# B2B_Connector.net
KiCad netlist of a schematic drawn in Altium Designer
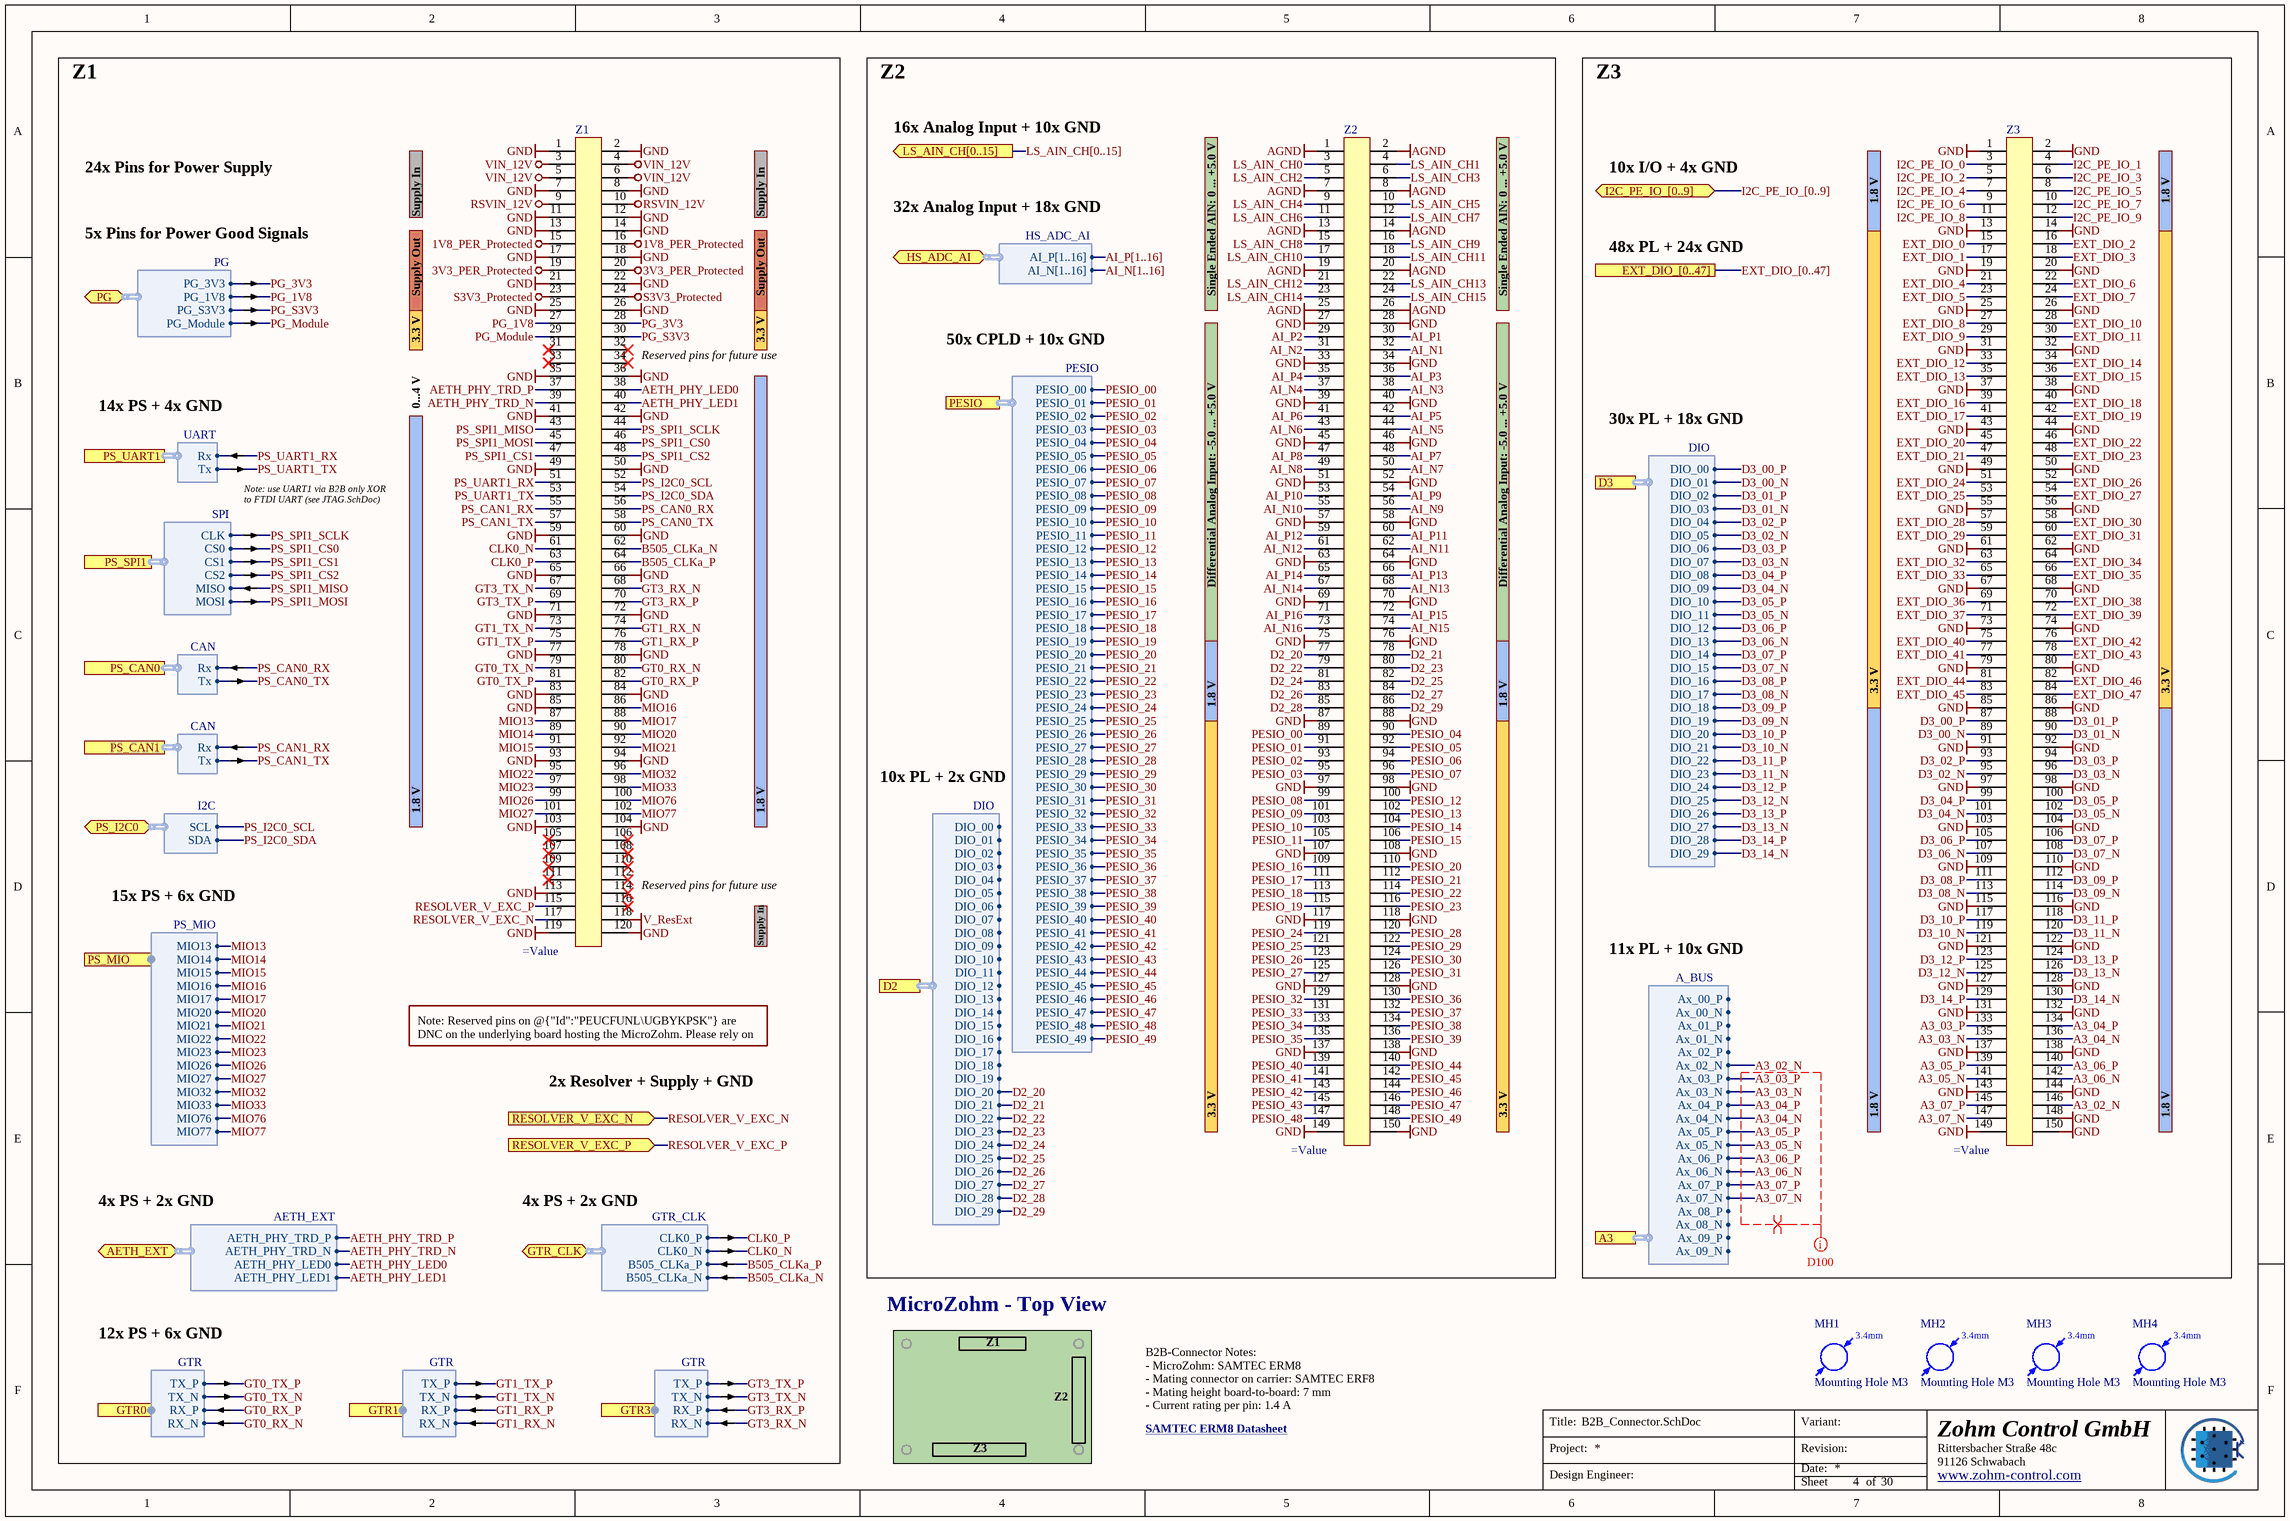
[diagram p0: B2B_Connector.SchDoc]

(export (version "E")
  (design (tool "Eeschema 10.0.6"))
  (components
    (comp (ref "MH1")
      (value "Mounting Hole M3")
      (footprint "MH_3.4")
      (description "Mounting Hole")
      (fields (field (name "CREATED FROM") "MHlatky"))
      (libsource (lib "user") (part "Mounting Hole"))
    )
    (comp (ref "MH2")
      (value "Mounting Hole M3")
      (footprint "MH_3.4")
      (description "Mounting Hole")
      (fields (field (name "CREATED FROM") "MHlatky"))
      (libsource (lib "user") (part "Mounting Hole"))
    )
    (comp (ref "MH3")
      (value "Mounting Hole M3")
      (footprint "MH_3.4")
      (description "Mounting Hole")
      (fields (field (name "CREATED FROM") "MHlatky"))
      (libsource (lib "user") (part "Mounting Hole"))
    )
    (comp (ref "MH4")
      (value "Mounting Hole M3")
      (footprint "MH_3.4")
      (description "Mounting Hole")
      (fields (field (name "CREATED FROM") "MHlatky"))
      (libsource (lib "user") (part "Mounting Hole"))
    )
    (comp (ref "Z1")
      (value "~")
      (footprint "ERM8-060-02.0-L-DV")
      (description "0.80 mm Edge Rate Rugged High Speed")
      (fields
        (field (name "MANUFACTURER PART NUMBER") "ERM8-060-02.0-L-DV-TR")
        (field (name "MANUFACTURER") "SAMTEC")
        (field (name "CREATED FROM") "AGeiger")
      )
      (libsource (lib "user") (part "CON-120"))
    )
    (comp (ref "Z2")
      (value "~")
      (footprint "ERM8-075-02.0-L-DV")
      (description "0.80 mm Edge Rate Rugged High Speed")
      (fields
        (field (name "MANUFACTURER PART NUMBER") "ERM8-075-02.0-L-DV-TR")
        (field (name "MANUFACTURER") "SAMTEC")
        (field (name "CREATED FROM") "AGeiger")
      )
      (libsource (lib "user") (part "CON-150"))
    )
    (comp (ref "Z3")
      (value "~")
      (footprint "ERM8-075-02.0-L-DV")
      (description "0.80 mm Edge Rate Rugged High Speed")
      (fields
        (field (name "MANUFACTURER PART NUMBER") "ERM8-075-02.0-L-DV-TR")
        (field (name "MANUFACTURER") "SAMTEC")
        (field (name "CREATED FROM") "AGeiger")
      )
      (libsource (lib "user") (part "CON-150"))
    )
  )
  (nets
    (net (code "14") (name "/A3_02_N") (class "Default")
      (node (ref "Z3") (pin "146") (pinfunction "146_146") (pintype "passive"))
    )
    (net (code "15") (name "/A3_03_N") (class "Default")
      (node (ref "Z3") (pin "135") (pinfunction "135_135") (pintype "passive"))
    )
    (net (code "16") (name "/A3_03_P") (class "Default")
      (node (ref "Z3") (pin "133") (pinfunction "133_133") (pintype "passive"))
    )
    (net (code "17") (name "/A3_04_N") (class "Default")
      (node (ref "Z3") (pin "136") (pinfunction "136_136") (pintype "passive"))
    )
    (net (code "18") (name "/A3_04_P") (class "Default")
      (node (ref "Z3") (pin "134") (pinfunction "134_134") (pintype "passive"))
    )
    (net (code "19") (name "/A3_05_N") (class "Default")
      (node (ref "Z3") (pin "141") (pinfunction "141_141") (pintype "passive"))
    )
    (net (code "20") (name "/A3_05_P") (class "Default")
      (node (ref "Z3") (pin "139") (pinfunction "139_139") (pintype "passive"))
    )
    (net (code "21") (name "/A3_06_N") (class "Default")
      (node (ref "Z3") (pin "142") (pinfunction "142_142") (pintype "passive"))
    )
    (net (code "22") (name "/A3_06_P") (class "Default")
      (node (ref "Z3") (pin "140") (pinfunction "140_140") (pintype "passive"))
    )
    (net (code "23") (name "/A3_07_N") (class "Default")
      (node (ref "Z3") (pin "147") (pinfunction "147_147") (pintype "passive"))
    )
    (net (code "24") (name "/A3_07_P") (class "Default")
      (node (ref "Z3") (pin "145") (pinfunction "145_145") (pintype "passive"))
    )
    (net (code "25") (name "/AETH_PHY_LED0") (class "Default")
      (node (ref "Z1") (pin "38") (pinfunction "38_38") (pintype "passive"))
    )
    (net (code "26") (name "/AETH_PHY_LED1") (class "Default")
      (node (ref "Z1") (pin "40") (pinfunction "40_40") (pintype "passive"))
    )
    (net (code "27") (name "/AETH_PHY_TRD_N") (class "Default")
      (node (ref "Z1") (pin "39") (pinfunction "39_39") (pintype "passive"))
    )
    (net (code "28") (name "/AETH_PHY_TRD_P") (class "Default")
      (node (ref "Z1") (pin "37") (pinfunction "37_37") (pintype "passive"))
    )
    (net (code "29") (name "/AI_N1") (class "Default")
      (node (ref "Z2") (pin "32") (pinfunction "32_32") (pintype "passive"))
    )
    (net (code "30") (name "/AI_N2") (class "Default")
      (node (ref "Z2") (pin "31") (pinfunction "31_31") (pintype "passive"))
    )
    (net (code "31") (name "/AI_N3") (class "Default")
      (node (ref "Z2") (pin "38") (pinfunction "38_38") (pintype "passive"))
    )
    (net (code "32") (name "/AI_N4") (class "Default")
      (node (ref "Z2") (pin "37") (pinfunction "37_37") (pintype "passive"))
    )
    (net (code "33") (name "/AI_N5") (class "Default")
      (node (ref "Z2") (pin "44") (pinfunction "44_44") (pintype "passive"))
    )
    (net (code "34") (name "/AI_N6") (class "Default")
      (node (ref "Z2") (pin "43") (pinfunction "43_43") (pintype "passive"))
    )
    (net (code "35") (name "/AI_N7") (class "Default")
      (node (ref "Z2") (pin "50") (pinfunction "50_50") (pintype "passive"))
    )
    (net (code "36") (name "/AI_N8") (class "Default")
      (node (ref "Z2") (pin "49") (pinfunction "49_49") (pintype "passive"))
    )
    (net (code "37") (name "/AI_N9") (class "Default")
      (node (ref "Z2") (pin "56") (pinfunction "56_56") (pintype "passive"))
    )
    (net (code "38") (name "/AI_N10") (class "Default")
      (node (ref "Z2") (pin "55") (pinfunction "55_55") (pintype "passive"))
    )
    (net (code "39") (name "/AI_N11") (class "Default")
      (node (ref "Z2") (pin "62") (pinfunction "62_62") (pintype "passive"))
    )
    (net (code "40") (name "/AI_N12") (class "Default")
      (node (ref "Z2") (pin "61") (pinfunction "61_61") (pintype "passive"))
    )
    (net (code "41") (name "/AI_N13") (class "Default")
      (node (ref "Z2") (pin "68") (pinfunction "68_68") (pintype "passive"))
    )
    (net (code "42") (name "/AI_N14") (class "Default")
      (node (ref "Z2") (pin "67") (pinfunction "67_67") (pintype "passive"))
    )
    (net (code "43") (name "/AI_N15") (class "Default")
      (node (ref "Z2") (pin "74") (pinfunction "74_74") (pintype "passive"))
    )
    (net (code "44") (name "/AI_N16") (class "Default")
      (node (ref "Z2") (pin "73") (pinfunction "73_73") (pintype "passive"))
    )
    (net (code "46") (name "/AI_P1") (class "Default")
      (node (ref "Z2") (pin "30") (pinfunction "30_30") (pintype "passive"))
    )
    (net (code "47") (name "/AI_P2") (class "Default")
      (node (ref "Z2") (pin "29") (pinfunction "29_29") (pintype "passive"))
    )
    (net (code "48") (name "/AI_P3") (class "Default")
      (node (ref "Z2") (pin "36") (pinfunction "36_36") (pintype "passive"))
    )
    (net (code "49") (name "/AI_P4") (class "Default")
      (node (ref "Z2") (pin "35") (pinfunction "35_35") (pintype "passive"))
    )
    (net (code "50") (name "/AI_P5") (class "Default")
      (node (ref "Z2") (pin "42") (pinfunction "42_42") (pintype "passive"))
    )
    (net (code "51") (name "/AI_P6") (class "Default")
      (node (ref "Z2") (pin "41") (pinfunction "41_41") (pintype "passive"))
    )
    (net (code "52") (name "/AI_P7") (class "Default")
      (node (ref "Z2") (pin "48") (pinfunction "48_48") (pintype "passive"))
    )
    (net (code "53") (name "/AI_P8") (class "Default")
      (node (ref "Z2") (pin "47") (pinfunction "47_47") (pintype "passive"))
    )
    (net (code "54") (name "/AI_P9") (class "Default")
      (node (ref "Z2") (pin "54") (pinfunction "54_54") (pintype "passive"))
    )
    (net (code "55") (name "/AI_P10") (class "Default")
      (node (ref "Z2") (pin "53") (pinfunction "53_53") (pintype "passive"))
    )
    (net (code "56") (name "/AI_P11") (class "Default")
      (node (ref "Z2") (pin "60") (pinfunction "60_60") (pintype "passive"))
    )
    (net (code "57") (name "/AI_P12") (class "Default")
      (node (ref "Z2") (pin "59") (pinfunction "59_59") (pintype "passive"))
    )
    (net (code "58") (name "/AI_P13") (class "Default")
      (node (ref "Z2") (pin "66") (pinfunction "66_66") (pintype "passive"))
    )
    (net (code "59") (name "/AI_P14") (class "Default")
      (node (ref "Z2") (pin "65") (pinfunction "65_65") (pintype "passive"))
    )
    (net (code "60") (name "/AI_P15") (class "Default")
      (node (ref "Z2") (pin "72") (pinfunction "72_72") (pintype "passive"))
    )
    (net (code "61") (name "/AI_P16") (class "Default")
      (node (ref "Z2") (pin "71") (pinfunction "71_71") (pintype "passive"))
    )
    (net (code "63") (name "/B505_CLKa_N") (class "Default")
      (node (ref "Z1") (pin "62") (pinfunction "62_62") (pintype "passive"))
    )
    (net (code "64") (name "/B505_CLKa_P") (class "Default")
      (node (ref "Z1") (pin "64") (pinfunction "64_64") (pintype "passive"))
    )
    (net (code "65") (name "/CLK0_N") (class "Default")
      (node (ref "Z1") (pin "61") (pinfunction "61_61") (pintype "passive"))
    )
    (net (code "66") (name "/CLK0_P") (class "Default")
      (node (ref "Z1") (pin "63") (pinfunction "63_63") (pintype "passive"))
    )
    (net (code "67") (name "/D2_20") (class "Default")
      (node (ref "Z2") (pin "77") (pinfunction "77_77") (pintype "passive"))
    )
    (net (code "68") (name "/D2_21") (class "Default")
      (node (ref "Z2") (pin "78") (pinfunction "78_78") (pintype "passive"))
    )
    (net (code "69") (name "/D2_22") (class "Default")
      (node (ref "Z2") (pin "79") (pinfunction "79_79") (pintype "passive"))
    )
    (net (code "70") (name "/D2_23") (class "Default")
      (node (ref "Z2") (pin "80") (pinfunction "80_80") (pintype "passive"))
    )
    (net (code "71") (name "/D2_24") (class "Default")
      (node (ref "Z2") (pin "81") (pinfunction "81_81") (pintype "passive"))
    )
    (net (code "72") (name "/D2_25") (class "Default")
      (node (ref "Z2") (pin "82") (pinfunction "82_82") (pintype "passive"))
    )
    (net (code "73") (name "/D2_26") (class "Default")
      (node (ref "Z2") (pin "83") (pinfunction "83_83") (pintype "passive"))
    )
    (net (code "74") (name "/D2_27") (class "Default")
      (node (ref "Z2") (pin "84") (pinfunction "84_84") (pintype "passive"))
    )
    (net (code "75") (name "/D2_28") (class "Default")
      (node (ref "Z2") (pin "85") (pinfunction "85_85") (pintype "passive"))
    )
    (net (code "76") (name "/D2_29") (class "Default")
      (node (ref "Z2") (pin "86") (pinfunction "86_86") (pintype "passive"))
    )
    (net (code "77") (name "/D3_00_N") (class "Default")
      (node (ref "Z3") (pin "89") (pinfunction "89_89") (pintype "passive"))
    )
    (net (code "78") (name "/D3_00_P") (class "Default")
      (node (ref "Z3") (pin "87") (pinfunction "87_87") (pintype "passive"))
    )
    (net (code "79") (name "/D3_01_N") (class "Default")
      (node (ref "Z3") (pin "90") (pinfunction "90_90") (pintype "passive"))
    )
    (net (code "80") (name "/D3_01_P") (class "Default")
      (node (ref "Z3") (pin "88") (pinfunction "88_88") (pintype "passive"))
    )
    (net (code "81") (name "/D3_02_N") (class "Default")
      (node (ref "Z3") (pin "95") (pinfunction "95_95") (pintype "passive"))
    )
    (net (code "82") (name "/D3_02_P") (class "Default")
      (node (ref "Z3") (pin "93") (pinfunction "93_93") (pintype "passive"))
    )
    (net (code "83") (name "/D3_03_N") (class "Default")
      (node (ref "Z3") (pin "96") (pinfunction "96_96") (pintype "passive"))
    )
    (net (code "84") (name "/D3_03_P") (class "Default")
      (node (ref "Z3") (pin "94") (pinfunction "94_94") (pintype "passive"))
    )
    (net (code "85") (name "/D3_04_N") (class "Default")
      (node (ref "Z3") (pin "101") (pinfunction "101_101") (pintype "passive"))
    )
    (net (code "86") (name "/D3_04_P") (class "Default")
      (node (ref "Z3") (pin "99") (pinfunction "99_99") (pintype "passive"))
    )
    (net (code "87") (name "/D3_05_N") (class "Default")
      (node (ref "Z3") (pin "102") (pinfunction "102_102") (pintype "passive"))
    )
    (net (code "88") (name "/D3_05_P") (class "Default")
      (node (ref "Z3") (pin "100") (pinfunction "100_100") (pintype "passive"))
    )
    (net (code "89") (name "/D3_06_N") (class "Default")
      (node (ref "Z3") (pin "107") (pinfunction "107_107") (pintype "passive"))
    )
    (net (code "90") (name "/D3_06_P") (class "Default")
      (node (ref "Z3") (pin "105") (pinfunction "105_105") (pintype "passive"))
    )
    (net (code "91") (name "/D3_07_N") (class "Default")
      (node (ref "Z3") (pin "108") (pinfunction "108_108") (pintype "passive"))
    )
    (net (code "92") (name "/D3_07_P") (class "Default")
      (node (ref "Z3") (pin "106") (pinfunction "106_106") (pintype "passive"))
    )
    (net (code "93") (name "/D3_08_N") (class "Default")
      (node (ref "Z3") (pin "113") (pinfunction "113_113") (pintype "passive"))
    )
    (net (code "94") (name "/D3_08_P") (class "Default")
      (node (ref "Z3") (pin "111") (pinfunction "111_111") (pintype "passive"))
    )
    (net (code "95") (name "/D3_09_N") (class "Default")
      (node (ref "Z3") (pin "114") (pinfunction "114_114") (pintype "passive"))
    )
    (net (code "96") (name "/D3_09_P") (class "Default")
      (node (ref "Z3") (pin "112") (pinfunction "112_112") (pintype "passive"))
    )
    (net (code "97") (name "/D3_10_N") (class "Default")
      (node (ref "Z3") (pin "119") (pinfunction "119_119") (pintype "passive"))
    )
    (net (code "98") (name "/D3_10_P") (class "Default")
      (node (ref "Z3") (pin "117") (pinfunction "117_117") (pintype "passive"))
    )
    (net (code "99") (name "/D3_11_N") (class "Default")
      (node (ref "Z3") (pin "120") (pinfunction "120_120") (pintype "passive"))
    )
    (net (code "100") (name "/D3_11_P") (class "Default")
      (node (ref "Z3") (pin "118") (pinfunction "118_118") (pintype "passive"))
    )
    (net (code "101") (name "/D3_12_N") (class "Default")
      (node (ref "Z3") (pin "125") (pinfunction "125_125") (pintype "passive"))
    )
    (net (code "102") (name "/D3_12_P") (class "Default")
      (node (ref "Z3") (pin "123") (pinfunction "123_123") (pintype "passive"))
    )
    (net (code "103") (name "/D3_13_N") (class "Default")
      (node (ref "Z3") (pin "126") (pinfunction "126_126") (pintype "passive"))
    )
    (net (code "104") (name "/D3_13_P") (class "Default")
      (node (ref "Z3") (pin "124") (pinfunction "124_124") (pintype "passive"))
    )
    (net (code "105") (name "/D3_14_N") (class "Default")
      (node (ref "Z3") (pin "130") (pinfunction "130_130") (pintype "passive"))
    )
    (net (code "106") (name "/D3_14_P") (class "Default")
      (node (ref "Z3") (pin "129") (pinfunction "129_129") (pintype "passive"))
    )
    (net (code "107") (name "/EXT_DIO_0") (class "Default")
      (node (ref "Z3") (pin "15") (pinfunction "15_15") (pintype "passive"))
    )
    (net (code "108") (name "/EXT_DIO_1") (class "Default")
      (node (ref "Z3") (pin "17") (pinfunction "17_17") (pintype "passive"))
    )
    (net (code "109") (name "/EXT_DIO_2") (class "Default")
      (node (ref "Z3") (pin "16") (pinfunction "16_16") (pintype "passive"))
    )
    (net (code "110") (name "/EXT_DIO_3") (class "Default")
      (node (ref "Z3") (pin "18") (pinfunction "18_18") (pintype "passive"))
    )
    (net (code "111") (name "/EXT_DIO_4") (class "Default")
      (node (ref "Z3") (pin "21") (pinfunction "21_21") (pintype "passive"))
    )
    (net (code "112") (name "/EXT_DIO_5") (class "Default")
      (node (ref "Z3") (pin "23") (pinfunction "23_23") (pintype "passive"))
    )
    (net (code "113") (name "/EXT_DIO_6") (class "Default")
      (node (ref "Z3") (pin "22") (pinfunction "22_22") (pintype "passive"))
    )
    (net (code "114") (name "/EXT_DIO_7") (class "Default")
      (node (ref "Z3") (pin "24") (pinfunction "24_24") (pintype "passive"))
    )
    (net (code "115") (name "/EXT_DIO_8") (class "Default")
      (node (ref "Z3") (pin "27") (pinfunction "27_27") (pintype "passive"))
    )
    (net (code "116") (name "/EXT_DIO_9") (class "Default")
      (node (ref "Z3") (pin "29") (pinfunction "29_29") (pintype "passive"))
    )
    (net (code "117") (name "/EXT_DIO_10") (class "Default")
      (node (ref "Z3") (pin "28") (pinfunction "28_28") (pintype "passive"))
    )
    (net (code "118") (name "/EXT_DIO_11") (class "Default")
      (node (ref "Z3") (pin "30") (pinfunction "30_30") (pintype "passive"))
    )
    (net (code "119") (name "/EXT_DIO_12") (class "Default")
      (node (ref "Z3") (pin "33") (pinfunction "33_33") (pintype "passive"))
    )
    (net (code "120") (name "/EXT_DIO_13") (class "Default")
      (node (ref "Z3") (pin "35") (pinfunction "35_35") (pintype "passive"))
    )
    (net (code "121") (name "/EXT_DIO_14") (class "Default")
      (node (ref "Z3") (pin "34") (pinfunction "34_34") (pintype "passive"))
    )
    (net (code "122") (name "/EXT_DIO_15") (class "Default")
      (node (ref "Z3") (pin "36") (pinfunction "36_36") (pintype "passive"))
    )
    (net (code "123") (name "/EXT_DIO_16") (class "Default")
      (node (ref "Z3") (pin "39") (pinfunction "39_39") (pintype "passive"))
    )
    (net (code "124") (name "/EXT_DIO_17") (class "Default")
      (node (ref "Z3") (pin "41") (pinfunction "41_41") (pintype "passive"))
    )
    (net (code "125") (name "/EXT_DIO_18") (class "Default")
      (node (ref "Z3") (pin "40") (pinfunction "40_40") (pintype "passive"))
    )
    (net (code "126") (name "/EXT_DIO_19") (class "Default")
      (node (ref "Z3") (pin "42") (pinfunction "42_42") (pintype "passive"))
    )
    (net (code "127") (name "/EXT_DIO_20") (class "Default")
      (node (ref "Z3") (pin "45") (pinfunction "45_45") (pintype "passive"))
    )
    (net (code "128") (name "/EXT_DIO_21") (class "Default")
      (node (ref "Z3") (pin "47") (pinfunction "47_47") (pintype "passive"))
    )
    (net (code "129") (name "/EXT_DIO_22") (class "Default")
      (node (ref "Z3") (pin "46") (pinfunction "46_46") (pintype "passive"))
    )
    (net (code "130") (name "/EXT_DIO_23") (class "Default")
      (node (ref "Z3") (pin "48") (pinfunction "48_48") (pintype "passive"))
    )
    (net (code "131") (name "/EXT_DIO_24") (class "Default")
      (node (ref "Z3") (pin "51") (pinfunction "51_51") (pintype "passive"))
    )
    (net (code "132") (name "/EXT_DIO_25") (class "Default")
      (node (ref "Z3") (pin "53") (pinfunction "53_53") (pintype "passive"))
    )
    (net (code "133") (name "/EXT_DIO_26") (class "Default")
      (node (ref "Z3") (pin "52") (pinfunction "52_52") (pintype "passive"))
    )
    (net (code "134") (name "/EXT_DIO_27") (class "Default")
      (node (ref "Z3") (pin "54") (pinfunction "54_54") (pintype "passive"))
    )
    (net (code "135") (name "/EXT_DIO_28") (class "Default")
      (node (ref "Z3") (pin "57") (pinfunction "57_57") (pintype "passive"))
    )
    (net (code "136") (name "/EXT_DIO_29") (class "Default")
      (node (ref "Z3") (pin "59") (pinfunction "59_59") (pintype "passive"))
    )
    (net (code "137") (name "/EXT_DIO_30") (class "Default")
      (node (ref "Z3") (pin "58") (pinfunction "58_58") (pintype "passive"))
    )
    (net (code "138") (name "/EXT_DIO_31") (class "Default")
      (node (ref "Z3") (pin "60") (pinfunction "60_60") (pintype "passive"))
    )
    (net (code "139") (name "/EXT_DIO_32") (class "Default")
      (node (ref "Z3") (pin "63") (pinfunction "63_63") (pintype "passive"))
    )
    (net (code "140") (name "/EXT_DIO_33") (class "Default")
      (node (ref "Z3") (pin "65") (pinfunction "65_65") (pintype "passive"))
    )
    (net (code "141") (name "/EXT_DIO_34") (class "Default")
      (node (ref "Z3") (pin "64") (pinfunction "64_64") (pintype "passive"))
    )
    (net (code "142") (name "/EXT_DIO_35") (class "Default")
      (node (ref "Z3") (pin "66") (pinfunction "66_66") (pintype "passive"))
    )
    (net (code "143") (name "/EXT_DIO_36") (class "Default")
      (node (ref "Z3") (pin "69") (pinfunction "69_69") (pintype "passive"))
    )
    (net (code "144") (name "/EXT_DIO_37") (class "Default")
      (node (ref "Z3") (pin "71") (pinfunction "71_71") (pintype "passive"))
    )
    (net (code "145") (name "/EXT_DIO_38") (class "Default")
      (node (ref "Z3") (pin "70") (pinfunction "70_70") (pintype "passive"))
    )
    (net (code "146") (name "/EXT_DIO_39") (class "Default")
      (node (ref "Z3") (pin "72") (pinfunction "72_72") (pintype "passive"))
    )
    (net (code "147") (name "/EXT_DIO_40") (class "Default")
      (node (ref "Z3") (pin "75") (pinfunction "75_75") (pintype "passive"))
    )
    (net (code "148") (name "/EXT_DIO_41") (class "Default")
      (node (ref "Z3") (pin "77") (pinfunction "77_77") (pintype "passive"))
    )
    (net (code "149") (name "/EXT_DIO_42") (class "Default")
      (node (ref "Z3") (pin "76") (pinfunction "76_76") (pintype "passive"))
    )
    (net (code "150") (name "/EXT_DIO_43") (class "Default")
      (node (ref "Z3") (pin "78") (pinfunction "78_78") (pintype "passive"))
    )
    (net (code "151") (name "/EXT_DIO_44") (class "Default")
      (node (ref "Z3") (pin "81") (pinfunction "81_81") (pintype "passive"))
    )
    (net (code "152") (name "/EXT_DIO_45") (class "Default")
      (node (ref "Z3") (pin "83") (pinfunction "83_83") (pintype "passive"))
    )
    (net (code "153") (name "/EXT_DIO_46") (class "Default")
      (node (ref "Z3") (pin "82") (pinfunction "82_82") (pintype "passive"))
    )
    (net (code "154") (name "/EXT_DIO_47") (class "Default")
      (node (ref "Z3") (pin "84") (pinfunction "84_84") (pintype "passive"))
    )
    (net (code "156") (name "/GT0_RX_N") (class "Default")
      (node (ref "Z1") (pin "80") (pinfunction "80_80") (pintype "passive"))
    )
    (net (code "157") (name "/GT0_RX_P") (class "Default")
      (node (ref "Z1") (pin "82") (pinfunction "82_82") (pintype "passive"))
    )
    (net (code "158") (name "/GT0_TX_N") (class "Default")
      (node (ref "Z1") (pin "79") (pinfunction "79_79") (pintype "passive"))
    )
    (net (code "159") (name "/GT0_TX_P") (class "Default")
      (node (ref "Z1") (pin "81") (pinfunction "81_81") (pintype "passive"))
    )
    (net (code "160") (name "/GT1_RX_N") (class "Default")
      (node (ref "Z1") (pin "74") (pinfunction "74_74") (pintype "passive"))
    )
    (net (code "161") (name "/GT1_RX_P") (class "Default")
      (node (ref "Z1") (pin "76") (pinfunction "76_76") (pintype "passive"))
    )
    (net (code "162") (name "/GT1_TX_N") (class "Default")
      (node (ref "Z1") (pin "73") (pinfunction "73_73") (pintype "passive"))
    )
    (net (code "163") (name "/GT1_TX_P") (class "Default")
      (node (ref "Z1") (pin "75") (pinfunction "75_75") (pintype "passive"))
    )
    (net (code "164") (name "/GT3_RX_N") (class "Default")
      (node (ref "Z1") (pin "68") (pinfunction "68_68") (pintype "passive"))
    )
    (net (code "165") (name "/GT3_RX_P") (class "Default")
      (node (ref "Z1") (pin "70") (pinfunction "70_70") (pintype "passive"))
    )
    (net (code "166") (name "/GT3_TX_N") (class "Default")
      (node (ref "Z1") (pin "67") (pinfunction "67_67") (pintype "passive"))
    )
    (net (code "167") (name "/GT3_TX_P") (class "Default")
      (node (ref "Z1") (pin "69") (pinfunction "69_69") (pintype "passive"))
    )
    (net (code "168") (name "/I2C_PE_IO_0") (class "Default")
      (node (ref "Z3") (pin "3") (pinfunction "3_3") (pintype "passive"))
    )
    (net (code "169") (name "/I2C_PE_IO_1") (class "Default")
      (node (ref "Z3") (pin "4") (pinfunction "4_4") (pintype "passive"))
    )
    (net (code "170") (name "/I2C_PE_IO_2") (class "Default")
      (node (ref "Z3") (pin "5") (pinfunction "5_5") (pintype "passive"))
    )
    (net (code "171") (name "/I2C_PE_IO_3") (class "Default")
      (node (ref "Z3") (pin "6") (pinfunction "6_6") (pintype "passive"))
    )
    (net (code "172") (name "/I2C_PE_IO_4") (class "Default")
      (node (ref "Z3") (pin "7") (pinfunction "7_7") (pintype "passive"))
    )
    (net (code "173") (name "/I2C_PE_IO_5") (class "Default")
      (node (ref "Z3") (pin "8") (pinfunction "8_8") (pintype "passive"))
    )
    (net (code "174") (name "/I2C_PE_IO_6") (class "Default")
      (node (ref "Z3") (pin "9") (pinfunction "9_9") (pintype "passive"))
    )
    (net (code "175") (name "/I2C_PE_IO_7") (class "Default")
      (node (ref "Z3") (pin "10") (pinfunction "10_10") (pintype "passive"))
    )
    (net (code "176") (name "/I2C_PE_IO_8") (class "Default")
      (node (ref "Z3") (pin "11") (pinfunction "11_11") (pintype "passive"))
    )
    (net (code "177") (name "/I2C_PE_IO_9") (class "Default")
      (node (ref "Z3") (pin "12") (pinfunction "12_12") (pintype "passive"))
    )
    (net (code "179") (name "/LS_AIN_CH0") (class "Default")
      (node (ref "Z2") (pin "3") (pinfunction "3_3") (pintype "passive"))
    )
    (net (code "180") (name "/LS_AIN_CH1") (class "Default")
      (node (ref "Z2") (pin "4") (pinfunction "4_4") (pintype "passive"))
    )
    (net (code "181") (name "/LS_AIN_CH2") (class "Default")
      (node (ref "Z2") (pin "5") (pinfunction "5_5") (pintype "passive"))
    )
    (net (code "182") (name "/LS_AIN_CH3") (class "Default")
      (node (ref "Z2") (pin "6") (pinfunction "6_6") (pintype "passive"))
    )
    (net (code "183") (name "/LS_AIN_CH4") (class "Default")
      (node (ref "Z2") (pin "9") (pinfunction "9_9") (pintype "passive"))
    )
    (net (code "184") (name "/LS_AIN_CH5") (class "Default")
      (node (ref "Z2") (pin "10") (pinfunction "10_10") (pintype "passive"))
    )
    (net (code "185") (name "/LS_AIN_CH6") (class "Default")
      (node (ref "Z2") (pin "11") (pinfunction "11_11") (pintype "passive"))
    )
    (net (code "186") (name "/LS_AIN_CH7") (class "Default")
      (node (ref "Z2") (pin "12") (pinfunction "12_12") (pintype "passive"))
    )
    (net (code "187") (name "/LS_AIN_CH8") (class "Default")
      (node (ref "Z2") (pin "15") (pinfunction "15_15") (pintype "passive"))
    )
    (net (code "188") (name "/LS_AIN_CH9") (class "Default")
      (node (ref "Z2") (pin "16") (pinfunction "16_16") (pintype "passive"))
    )
    (net (code "189") (name "/LS_AIN_CH10") (class "Default")
      (node (ref "Z2") (pin "17") (pinfunction "17_17") (pintype "passive"))
    )
    (net (code "190") (name "/LS_AIN_CH11") (class "Default")
      (node (ref "Z2") (pin "18") (pinfunction "18_18") (pintype "passive"))
    )
    (net (code "191") (name "/LS_AIN_CH12") (class "Default")
      (node (ref "Z2") (pin "21") (pinfunction "21_21") (pintype "passive"))
    )
    (net (code "192") (name "/LS_AIN_CH13") (class "Default")
      (node (ref "Z2") (pin "22") (pinfunction "22_22") (pintype "passive"))
    )
    (net (code "193") (name "/LS_AIN_CH14") (class "Default")
      (node (ref "Z2") (pin "23") (pinfunction "23_23") (pintype "passive"))
    )
    (net (code "194") (name "/LS_AIN_CH15") (class "Default")
      (node (ref "Z2") (pin "24") (pinfunction "24_24") (pintype "passive"))
    )
    (net (code "196") (name "/MIO13") (class "Default")
      (node (ref "Z1") (pin "87") (pinfunction "87_87") (pintype "passive"))
    )
    (net (code "197") (name "/MIO14") (class "Default")
      (node (ref "Z1") (pin "89") (pinfunction "89_89") (pintype "passive"))
    )
    (net (code "198") (name "/MIO15") (class "Default")
      (node (ref "Z1") (pin "91") (pinfunction "91_91") (pintype "passive"))
    )
    (net (code "199") (name "/MIO16") (class "Default")
      (node (ref "Z1") (pin "86") (pinfunction "86_86") (pintype "passive"))
    )
    (net (code "200") (name "/MIO17") (class "Default")
      (node (ref "Z1") (pin "88") (pinfunction "88_88") (pintype "passive"))
    )
    (net (code "201") (name "/MIO20") (class "Default")
      (node (ref "Z1") (pin "90") (pinfunction "90_90") (pintype "passive"))
    )
    (net (code "202") (name "/MIO21") (class "Default")
      (node (ref "Z1") (pin "92") (pinfunction "92_92") (pintype "passive"))
    )
    (net (code "203") (name "/MIO22") (class "Default")
      (node (ref "Z1") (pin "95") (pinfunction "95_95") (pintype "passive"))
    )
    (net (code "204") (name "/MIO23") (class "Default")
      (node (ref "Z1") (pin "97") (pinfunction "97_97") (pintype "passive"))
    )
    (net (code "205") (name "/MIO26") (class "Default")
      (node (ref "Z1") (pin "99") (pinfunction "99_99") (pintype "passive"))
    )
    (net (code "206") (name "/MIO27") (class "Default")
      (node (ref "Z1") (pin "101") (pinfunction "101_101") (pintype "passive"))
    )
    (net (code "207") (name "/MIO32") (class "Default")
      (node (ref "Z1") (pin "96") (pinfunction "96_96") (pintype "passive"))
    )
    (net (code "208") (name "/MIO33") (class "Default")
      (node (ref "Z1") (pin "98") (pinfunction "98_98") (pintype "passive"))
    )
    (net (code "209") (name "/MIO76") (class "Default")
      (node (ref "Z1") (pin "100") (pinfunction "100_100") (pintype "passive"))
    )
    (net (code "210") (name "/MIO77") (class "Default")
      (node (ref "Z1") (pin "102") (pinfunction "102_102") (pintype "passive"))
    )
    (net (code "211") (name "/PESIO_00") (class "Default")
      (node (ref "Z2") (pin "89") (pinfunction "89_89") (pintype "passive"))
    )
    (net (code "212") (name "/PESIO_01") (class "Default")
      (node (ref "Z2") (pin "91") (pinfunction "91_91") (pintype "passive"))
    )
    (net (code "213") (name "/PESIO_02") (class "Default")
      (node (ref "Z2") (pin "93") (pinfunction "93_93") (pintype "passive"))
    )
    (net (code "214") (name "/PESIO_03") (class "Default")
      (node (ref "Z2") (pin "95") (pinfunction "95_95") (pintype "passive"))
    )
    (net (code "215") (name "/PESIO_04") (class "Default")
      (node (ref "Z2") (pin "90") (pinfunction "90_90") (pintype "passive"))
    )
    (net (code "216") (name "/PESIO_05") (class "Default")
      (node (ref "Z2") (pin "92") (pinfunction "92_92") (pintype "passive"))
    )
    (net (code "217") (name "/PESIO_06") (class "Default")
      (node (ref "Z2") (pin "94") (pinfunction "94_94") (pintype "passive"))
    )
    (net (code "218") (name "/PESIO_07") (class "Default")
      (node (ref "Z2") (pin "96") (pinfunction "96_96") (pintype "passive"))
    )
    (net (code "219") (name "/PESIO_08") (class "Default")
      (node (ref "Z2") (pin "99") (pinfunction "99_99") (pintype "passive"))
    )
    (net (code "220") (name "/PESIO_09") (class "Default")
      (node (ref "Z2") (pin "101") (pinfunction "101_101") (pintype "passive"))
    )
    (net (code "221") (name "/PESIO_10") (class "Default")
      (node (ref "Z2") (pin "103") (pinfunction "103_103") (pintype "passive"))
    )
    (net (code "222") (name "/PESIO_11") (class "Default")
      (node (ref "Z2") (pin "105") (pinfunction "105_105") (pintype "passive"))
    )
    (net (code "223") (name "/PESIO_12") (class "Default")
      (node (ref "Z2") (pin "100") (pinfunction "100_100") (pintype "passive"))
    )
    (net (code "224") (name "/PESIO_13") (class "Default")
      (node (ref "Z2") (pin "102") (pinfunction "102_102") (pintype "passive"))
    )
    (net (code "225") (name "/PESIO_14") (class "Default")
      (node (ref "Z2") (pin "104") (pinfunction "104_104") (pintype "passive"))
    )
    (net (code "226") (name "/PESIO_15") (class "Default")
      (node (ref "Z2") (pin "106") (pinfunction "106_106") (pintype "passive"))
    )
    (net (code "227") (name "/PESIO_16") (class "Default")
      (node (ref "Z2") (pin "109") (pinfunction "109_109") (pintype "passive"))
    )
    (net (code "228") (name "/PESIO_17") (class "Default")
      (node (ref "Z2") (pin "111") (pinfunction "111_111") (pintype "passive"))
    )
    (net (code "229") (name "/PESIO_18") (class "Default")
      (node (ref "Z2") (pin "113") (pinfunction "113_113") (pintype "passive"))
    )
    (net (code "230") (name "/PESIO_19") (class "Default")
      (node (ref "Z2") (pin "115") (pinfunction "115_115") (pintype "passive"))
    )
    (net (code "231") (name "/PESIO_20") (class "Default")
      (node (ref "Z2") (pin "110") (pinfunction "110_110") (pintype "passive"))
    )
    (net (code "232") (name "/PESIO_21") (class "Default")
      (node (ref "Z2") (pin "112") (pinfunction "112_112") (pintype "passive"))
    )
    (net (code "233") (name "/PESIO_22") (class "Default")
      (node (ref "Z2") (pin "114") (pinfunction "114_114") (pintype "passive"))
    )
    (net (code "234") (name "/PESIO_23") (class "Default")
      (node (ref "Z2") (pin "116") (pinfunction "116_116") (pintype "passive"))
    )
    (net (code "235") (name "/PESIO_24") (class "Default")
      (node (ref "Z2") (pin "119") (pinfunction "119_119") (pintype "passive"))
    )
    (net (code "236") (name "/PESIO_25") (class "Default")
      (node (ref "Z2") (pin "121") (pinfunction "121_121") (pintype "passive"))
    )
    (net (code "237") (name "/PESIO_26") (class "Default")
      (node (ref "Z2") (pin "123") (pinfunction "123_123") (pintype "passive"))
    )
    (net (code "238") (name "/PESIO_27") (class "Default")
      (node (ref "Z2") (pin "125") (pinfunction "125_125") (pintype "passive"))
    )
    (net (code "239") (name "/PESIO_28") (class "Default")
      (node (ref "Z2") (pin "120") (pinfunction "120_120") (pintype "passive"))
    )
    (net (code "240") (name "/PESIO_29") (class "Default")
      (node (ref "Z2") (pin "122") (pinfunction "122_122") (pintype "passive"))
    )
    (net (code "241") (name "/PESIO_30") (class "Default")
      (node (ref "Z2") (pin "124") (pinfunction "124_124") (pintype "passive"))
    )
    (net (code "242") (name "/PESIO_31") (class "Default")
      (node (ref "Z2") (pin "126") (pinfunction "126_126") (pintype "passive"))
    )
    (net (code "243") (name "/PESIO_32") (class "Default")
      (node (ref "Z2") (pin "129") (pinfunction "129_129") (pintype "passive"))
    )
    (net (code "244") (name "/PESIO_33") (class "Default")
      (node (ref "Z2") (pin "131") (pinfunction "131_131") (pintype "passive"))
    )
    (net (code "245") (name "/PESIO_34") (class "Default")
      (node (ref "Z2") (pin "133") (pinfunction "133_133") (pintype "passive"))
    )
    (net (code "246") (name "/PESIO_35") (class "Default")
      (node (ref "Z2") (pin "135") (pinfunction "135_135") (pintype "passive"))
    )
    (net (code "247") (name "/PESIO_36") (class "Default")
      (node (ref "Z2") (pin "130") (pinfunction "130_130") (pintype "passive"))
    )
    (net (code "248") (name "/PESIO_37") (class "Default")
      (node (ref "Z2") (pin "132") (pinfunction "132_132") (pintype "passive"))
    )
    (net (code "249") (name "/PESIO_38") (class "Default")
      (node (ref "Z2") (pin "134") (pinfunction "134_134") (pintype "passive"))
    )
    (net (code "250") (name "/PESIO_39") (class "Default")
      (node (ref "Z2") (pin "136") (pinfunction "136_136") (pintype "passive"))
    )
    (net (code "251") (name "/PESIO_40") (class "Default")
      (node (ref "Z2") (pin "139") (pinfunction "139_139") (pintype "passive"))
    )
    (net (code "252") (name "/PESIO_41") (class "Default")
      (node (ref "Z2") (pin "141") (pinfunction "141_141") (pintype "passive"))
    )
    (net (code "253") (name "/PESIO_42") (class "Default")
      (node (ref "Z2") (pin "143") (pinfunction "143_143") (pintype "passive"))
    )
    (net (code "254") (name "/PESIO_43") (class "Default")
      (node (ref "Z2") (pin "145") (pinfunction "145_145") (pintype "passive"))
    )
    (net (code "255") (name "/PESIO_44") (class "Default")
      (node (ref "Z2") (pin "140") (pinfunction "140_140") (pintype "passive"))
    )
    (net (code "256") (name "/PESIO_45") (class "Default")
      (node (ref "Z2") (pin "142") (pinfunction "142_142") (pintype "passive"))
    )
    (net (code "257") (name "/PESIO_46") (class "Default")
      (node (ref "Z2") (pin "144") (pinfunction "144_144") (pintype "passive"))
    )
    (net (code "258") (name "/PESIO_47") (class "Default")
      (node (ref "Z2") (pin "146") (pinfunction "146_146") (pintype "passive"))
    )
    (net (code "259") (name "/PESIO_48") (class "Default")
      (node (ref "Z2") (pin "147") (pinfunction "147_147") (pintype "passive"))
    )
    (net (code "260") (name "/PESIO_49") (class "Default")
      (node (ref "Z2") (pin "148") (pinfunction "148_148") (pintype "passive"))
    )
    (net (code "261") (name "/PG_1V8") (class "Default")
      (node (ref "Z1") (pin "27") (pinfunction "27_27") (pintype "passive"))
    )
    (net (code "262") (name "/PG_3V3") (class "Default")
      (node (ref "Z1") (pin "28") (pinfunction "28_28") (pintype "passive"))
    )
    (net (code "263") (name "/PG_Module") (class "Default")
      (node (ref "Z1") (pin "29") (pinfunction "29_29") (pintype "passive"))
    )
    (net (code "264") (name "/PG_S3V3") (class "Default")
      (node (ref "Z1") (pin "30") (pinfunction "30_30") (pintype "passive"))
    )
    (net (code "265") (name "/PS_CAN0_RX") (class "Default")
      (node (ref "Z1") (pin "56") (pinfunction "56_56") (pintype "passive"))
    )
    (net (code "266") (name "/PS_CAN0_TX") (class "Default")
      (node (ref "Z1") (pin "58") (pinfunction "58_58") (pintype "passive"))
    )
    (net (code "267") (name "/PS_CAN1_RX") (class "Default")
      (node (ref "Z1") (pin "55") (pinfunction "55_55") (pintype "passive"))
    )
    (net (code "268") (name "/PS_CAN1_TX") (class "Default")
      (node (ref "Z1") (pin "57") (pinfunction "57_57") (pintype "passive"))
    )
    (net (code "269") (name "/PS_I2C0_SCL") (class "Default")
      (node (ref "Z1") (pin "52") (pinfunction "52_52") (pintype "passive"))
    )
    (net (code "270") (name "/PS_I2C0_SDA") (class "Default")
      (node (ref "Z1") (pin "54") (pinfunction "54_54") (pintype "passive"))
    )
    (net (code "271") (name "/PS_SPI1_CS0") (class "Default")
      (node (ref "Z1") (pin "46") (pinfunction "46_46") (pintype "passive"))
    )
    (net (code "272") (name "/PS_SPI1_CS1") (class "Default")
      (node (ref "Z1") (pin "47") (pinfunction "47_47") (pintype "passive"))
    )
    (net (code "273") (name "/PS_SPI1_CS2") (class "Default")
      (node (ref "Z1") (pin "48") (pinfunction "48_48") (pintype "passive"))
    )
    (net (code "274") (name "/PS_SPI1_MISO") (class "Default")
      (node (ref "Z1") (pin "43") (pinfunction "43_43") (pintype "passive"))
    )
    (net (code "275") (name "/PS_SPI1_MOSI") (class "Default")
      (node (ref "Z1") (pin "45") (pinfunction "45_45") (pintype "passive"))
    )
    (net (code "276") (name "/PS_SPI1_SCLK") (class "Default")
      (node (ref "Z1") (pin "44") (pinfunction "44_44") (pintype "passive"))
    )
    (net (code "277") (name "/PS_UART1_RX") (class "Default")
      (node (ref "Z1") (pin "51") (pinfunction "51_51") (pintype "passive"))
    )
    (net (code "278") (name "/PS_UART1_TX") (class "Default")
      (node (ref "Z1") (pin "53") (pinfunction "53_53") (pintype "passive"))
    )
    (net (code "279") (name "/RESOLVER_V_EXC_N") (class "Default")
      (node (ref "Z1") (pin "117") (pinfunction "117_117") (pintype "passive"))
    )
    (net (code "280") (name "/RESOLVER_V_EXC_P") (class "Default")
      (node (ref "Z1") (pin "115") (pinfunction "115_115") (pintype "passive"))
    )
    (net (code "294") (name "1V8_PER_Protected") (class "Default")
      (node (ref "Z1") (pin "15") (pinfunction "15_15") (pintype "passive"))
      (node (ref "Z1") (pin "16") (pinfunction "16_16") (pintype "passive"))
    )
    (net (code "295") (name "3V3_PER_Protected") (class "Default")
      (node (ref "Z1") (pin "19") (pinfunction "19_19") (pintype "passive"))
      (node (ref "Z1") (pin "20") (pinfunction "20_20") (pintype "passive"))
    )
    (net (code "296") (name "AGND") (class "Default")
      (node (ref "Z2") (pin "1") (pinfunction "1_1") (pintype "passive"))
      (node (ref "Z2") (pin "13") (pinfunction "13_13") (pintype "passive"))
      (node (ref "Z2") (pin "14") (pinfunction "14_14") (pintype "passive"))
      (node (ref "Z2") (pin "19") (pinfunction "19_19") (pintype "passive"))
      (node (ref "Z2") (pin "2") (pinfunction "2_2") (pintype "passive"))
      (node (ref "Z2") (pin "20") (pinfunction "20_20") (pintype "passive"))
      (node (ref "Z2") (pin "25") (pinfunction "25_25") (pintype "passive"))
      (node (ref "Z2") (pin "26") (pinfunction "26_26") (pintype "passive"))
      (node (ref "Z2") (pin "7") (pinfunction "7_7") (pintype "passive"))
      (node (ref "Z2") (pin "8") (pinfunction "8_8") (pintype "passive"))
    )
    (net (code "297") (name "GND") (class "Default")
      (node (ref "Z1") (pin "1") (pinfunction "1_1") (pintype "passive"))
      (node (ref "Z1") (pin "103") (pinfunction "103_103") (pintype "passive"))
      (node (ref "Z1") (pin "104") (pinfunction "104_104") (pintype "passive"))
      (node (ref "Z1") (pin "11") (pinfunction "11_11") (pintype "passive"))
      (node (ref "Z1") (pin "113") (pinfunction "113_113") (pintype "passive"))
      (node (ref "Z1") (pin "119") (pinfunction "119_119") (pintype "passive"))
      (node (ref "Z1") (pin "12") (pinfunction "12_12") (pintype "passive"))
      (node (ref "Z1") (pin "120") (pinfunction "120_120") (pintype "passive"))
      (node (ref "Z1") (pin "13") (pinfunction "13_13") (pintype "passive"))
      (node (ref "Z1") (pin "14") (pinfunction "14_14") (pintype "passive"))
      (node (ref "Z1") (pin "17") (pinfunction "17_17") (pintype "passive"))
      (node (ref "Z1") (pin "18") (pinfunction "18_18") (pintype "passive"))
      (node (ref "Z1") (pin "2") (pinfunction "2_2") (pintype "passive"))
      (node (ref "Z1") (pin "21") (pinfunction "21_21") (pintype "passive"))
      (node (ref "Z1") (pin "22") (pinfunction "22_22") (pintype "passive"))
      (node (ref "Z1") (pin "25") (pinfunction "25_25") (pintype "passive"))
      (node (ref "Z1") (pin "26") (pinfunction "26_26") (pintype "passive"))
      (node (ref "Z1") (pin "35") (pinfunction "35_35") (pintype "passive"))
      (node (ref "Z1") (pin "36") (pinfunction "36_36") (pintype "passive"))
      (node (ref "Z1") (pin "41") (pinfunction "41_41") (pintype "passive"))
      (node (ref "Z1") (pin "42") (pinfunction "42_42") (pintype "passive"))
      (node (ref "Z1") (pin "49") (pinfunction "49_49") (pintype "passive"))
      (node (ref "Z1") (pin "50") (pinfunction "50_50") (pintype "passive"))
      (node (ref "Z1") (pin "59") (pinfunction "59_59") (pintype "passive"))
      (node (ref "Z1") (pin "60") (pinfunction "60_60") (pintype "passive"))
      (node (ref "Z1") (pin "65") (pinfunction "65_65") (pintype "passive"))
      (node (ref "Z1") (pin "66") (pinfunction "66_66") (pintype "passive"))
      (node (ref "Z1") (pin "7") (pinfunction "7_7") (pintype "passive"))
      (node (ref "Z1") (pin "71") (pinfunction "71_71") (pintype "passive"))
      (node (ref "Z1") (pin "72") (pinfunction "72_72") (pintype "passive"))
      (node (ref "Z1") (pin "77") (pinfunction "77_77") (pintype "passive"))
      (node (ref "Z1") (pin "78") (pinfunction "78_78") (pintype "passive"))
      (node (ref "Z1") (pin "8") (pinfunction "8_8") (pintype "passive"))
      (node (ref "Z1") (pin "83") (pinfunction "83_83") (pintype "passive"))
      (node (ref "Z1") (pin "84") (pinfunction "84_84") (pintype "passive"))
      (node (ref "Z1") (pin "85") (pinfunction "85_85") (pintype "passive"))
      (node (ref "Z1") (pin "93") (pinfunction "93_93") (pintype "passive"))
      (node (ref "Z1") (pin "94") (pinfunction "94_94") (pintype "passive"))
      (node (ref "Z2") (pin "107") (pinfunction "107_107") (pintype "passive"))
      (node (ref "Z2") (pin "108") (pinfunction "108_108") (pintype "passive"))
      (node (ref "Z2") (pin "117") (pinfunction "117_117") (pintype "passive"))
      (node (ref "Z2") (pin "118") (pinfunction "118_118") (pintype "passive"))
      (node (ref "Z2") (pin "127") (pinfunction "127_127") (pintype "passive"))
      (node (ref "Z2") (pin "128") (pinfunction "128_128") (pintype "passive"))
      (node (ref "Z2") (pin "137") (pinfunction "137_137") (pintype "passive"))
      (node (ref "Z2") (pin "138") (pinfunction "138_138") (pintype "passive"))
      (node (ref "Z2") (pin "149") (pinfunction "149_149") (pintype "passive"))
      (node (ref "Z2") (pin "150") (pinfunction "150_150") (pintype "passive"))
      (node (ref "Z2") (pin "27") (pinfunction "27_27") (pintype "passive"))
      (node (ref "Z2") (pin "28") (pinfunction "28_28") (pintype "passive"))
      (node (ref "Z2") (pin "33") (pinfunction "33_33") (pintype "passive"))
      (node (ref "Z2") (pin "34") (pinfunction "34_34") (pintype "passive"))
      (node (ref "Z2") (pin "39") (pinfunction "39_39") (pintype "passive"))
      (node (ref "Z2") (pin "40") (pinfunction "40_40") (pintype "passive"))
      (node (ref "Z2") (pin "45") (pinfunction "45_45") (pintype "passive"))
      (node (ref "Z2") (pin "46") (pinfunction "46_46") (pintype "passive"))
      (node (ref "Z2") (pin "51") (pinfunction "51_51") (pintype "passive"))
      (node (ref "Z2") (pin "52") (pinfunction "52_52") (pintype "passive"))
      (node (ref "Z2") (pin "57") (pinfunction "57_57") (pintype "passive"))
      (node (ref "Z2") (pin "58") (pinfunction "58_58") (pintype "passive"))
      (node (ref "Z2") (pin "63") (pinfunction "63_63") (pintype "passive"))
      (node (ref "Z2") (pin "64") (pinfunction "64_64") (pintype "passive"))
      (node (ref "Z2") (pin "69") (pinfunction "69_69") (pintype "passive"))
      (node (ref "Z2") (pin "70") (pinfunction "70_70") (pintype "passive"))
      (node (ref "Z2") (pin "75") (pinfunction "75_75") (pintype "passive"))
      (node (ref "Z2") (pin "76") (pinfunction "76_76") (pintype "passive"))
      (node (ref "Z2") (pin "87") (pinfunction "87_87") (pintype "passive"))
      (node (ref "Z2") (pin "88") (pinfunction "88_88") (pintype "passive"))
      (node (ref "Z2") (pin "97") (pinfunction "97_97") (pintype "passive"))
      (node (ref "Z2") (pin "98") (pinfunction "98_98") (pintype "passive"))
      (node (ref "Z3") (pin "1") (pinfunction "1_1") (pintype "passive"))
      (node (ref "Z3") (pin "103") (pinfunction "103_103") (pintype "passive"))
      (node (ref "Z3") (pin "104") (pinfunction "104_104") (pintype "passive"))
      (node (ref "Z3") (pin "109") (pinfunction "109_109") (pintype "passive"))
      (node (ref "Z3") (pin "110") (pinfunction "110_110") (pintype "passive"))
      (node (ref "Z3") (pin "115") (pinfunction "115_115") (pintype "passive"))
      (node (ref "Z3") (pin "116") (pinfunction "116_116") (pintype "passive"))
      (node (ref "Z3") (pin "121") (pinfunction "121_121") (pintype "passive"))
      (node (ref "Z3") (pin "122") (pinfunction "122_122") (pintype "passive"))
      (node (ref "Z3") (pin "127") (pinfunction "127_127") (pintype "passive"))
      (node (ref "Z3") (pin "128") (pinfunction "128_128") (pintype "passive"))
      (node (ref "Z3") (pin "13") (pinfunction "13_13") (pintype "passive"))
      (node (ref "Z3") (pin "131") (pinfunction "131_131") (pintype "passive"))
      (node (ref "Z3") (pin "132") (pinfunction "132_132") (pintype "passive"))
      (node (ref "Z3") (pin "137") (pinfunction "137_137") (pintype "passive"))
      (node (ref "Z3") (pin "138") (pinfunction "138_138") (pintype "passive"))
      (node (ref "Z3") (pin "14") (pinfunction "14_14") (pintype "passive"))
      (node (ref "Z3") (pin "143") (pinfunction "143_143") (pintype "passive"))
      (node (ref "Z3") (pin "144") (pinfunction "144_144") (pintype "passive"))
      (node (ref "Z3") (pin "148") (pinfunction "148_148") (pintype "passive"))
      (node (ref "Z3") (pin "149") (pinfunction "149_149") (pintype "passive"))
      (node (ref "Z3") (pin "150") (pinfunction "150_150") (pintype "passive"))
      (node (ref "Z3") (pin "19") (pinfunction "19_19") (pintype "passive"))
      (node (ref "Z3") (pin "2") (pinfunction "2_2") (pintype "passive"))
      (node (ref "Z3") (pin "20") (pinfunction "20_20") (pintype "passive"))
      (node (ref "Z3") (pin "25") (pinfunction "25_25") (pintype "passive"))
      (node (ref "Z3") (pin "26") (pinfunction "26_26") (pintype "passive"))
      (node (ref "Z3") (pin "31") (pinfunction "31_31") (pintype "passive"))
      (node (ref "Z3") (pin "32") (pinfunction "32_32") (pintype "passive"))
      (node (ref "Z3") (pin "37") (pinfunction "37_37") (pintype "passive"))
      (node (ref "Z3") (pin "38") (pinfunction "38_38") (pintype "passive"))
      (node (ref "Z3") (pin "43") (pinfunction "43_43") (pintype "passive"))
      (node (ref "Z3") (pin "44") (pinfunction "44_44") (pintype "passive"))
      (node (ref "Z3") (pin "49") (pinfunction "49_49") (pintype "passive"))
      (node (ref "Z3") (pin "50") (pinfunction "50_50") (pintype "passive"))
      (node (ref "Z3") (pin "55") (pinfunction "55_55") (pintype "passive"))
      (node (ref "Z3") (pin "56") (pinfunction "56_56") (pintype "passive"))
      (node (ref "Z3") (pin "61") (pinfunction "61_61") (pintype "passive"))
      (node (ref "Z3") (pin "62") (pinfunction "62_62") (pintype "passive"))
      (node (ref "Z3") (pin "67") (pinfunction "67_67") (pintype "passive"))
      (node (ref "Z3") (pin "68") (pinfunction "68_68") (pintype "passive"))
      (node (ref "Z3") (pin "73") (pinfunction "73_73") (pintype "passive"))
      (node (ref "Z3") (pin "74") (pinfunction "74_74") (pintype "passive"))
      (node (ref "Z3") (pin "79") (pinfunction "79_79") (pintype "passive"))
      (node (ref "Z3") (pin "80") (pinfunction "80_80") (pintype "passive"))
      (node (ref "Z3") (pin "85") (pinfunction "85_85") (pintype "passive"))
      (node (ref "Z3") (pin "86") (pinfunction "86_86") (pintype "passive"))
      (node (ref "Z3") (pin "91") (pinfunction "91_91") (pintype "passive"))
      (node (ref "Z3") (pin "92") (pinfunction "92_92") (pintype "passive"))
      (node (ref "Z3") (pin "97") (pinfunction "97_97") (pintype "passive"))
      (node (ref "Z3") (pin "98") (pinfunction "98_98") (pintype "passive"))
    )
    (net (code "298") (name "RSVIN_12V") (class "Default")
      (node (ref "Z1") (pin "10") (pinfunction "10_10") (pintype "passive"))
      (node (ref "Z1") (pin "9") (pinfunction "9_9") (pintype "passive"))
    )
    (net (code "299") (name "S3V3_Protected") (class "Default")
      (node (ref "Z1") (pin "23") (pinfunction "23_23") (pintype "passive"))
      (node (ref "Z1") (pin "24") (pinfunction "24_24") (pintype "passive"))
    )
    (net (code "300") (name "VIN_12V") (class "Default")
      (node (ref "Z1") (pin "3") (pinfunction "3_3") (pintype "passive"))
      (node (ref "Z1") (pin "4") (pinfunction "4_4") (pintype "passive"))
      (node (ref "Z1") (pin "5") (pinfunction "5_5") (pintype "passive"))
      (node (ref "Z1") (pin "6") (pinfunction "6_6") (pintype "passive"))
    )
    (net (code "301") (name "V_ResExt") (class "Default")
      (node (ref "Z1") (pin "118") (pinfunction "118_118") (pintype "passive"))
    )
    (net (code "302") (name "unconnected-(Z1-Pad31)") (class "Default")
      (node (ref "Z1") (pin "31") (pinfunction "31_31") (pintype "passive+no_connect"))
    )
    (net (code "303") (name "unconnected-(Z1-Pad32)") (class "Default")
      (node (ref "Z1") (pin "32") (pinfunction "32_32") (pintype "passive+no_connect"))
    )
    (net (code "304") (name "unconnected-(Z1-Pad33)") (class "Default")
      (node (ref "Z1") (pin "33") (pinfunction "33_33") (pintype "passive+no_connect"))
    )
    (net (code "305") (name "unconnected-(Z1-Pad34)") (class "Default")
      (node (ref "Z1") (pin "34") (pinfunction "34_34") (pintype "passive+no_connect"))
    )
    (net (code "306") (name "unconnected-(Z1-Pad105)") (class "Default")
      (node (ref "Z1") (pin "105") (pinfunction "105_105") (pintype "passive+no_connect"))
    )
    (net (code "307") (name "unconnected-(Z1-Pad106)") (class "Default")
      (node (ref "Z1") (pin "106") (pinfunction "106_106") (pintype "passive+no_connect"))
    )
    (net (code "308") (name "unconnected-(Z1-Pad107)") (class "Default")
      (node (ref "Z1") (pin "107") (pinfunction "107_107") (pintype "passive+no_connect"))
    )
    (net (code "309") (name "unconnected-(Z1-Pad108)") (class "Default")
      (node (ref "Z1") (pin "108") (pinfunction "108_108") (pintype "passive+no_connect"))
    )
    (net (code "310") (name "unconnected-(Z1-Pad109)") (class "Default")
      (node (ref "Z1") (pin "109") (pinfunction "109_109") (pintype "passive+no_connect"))
    )
    (net (code "311") (name "unconnected-(Z1-Pad110)") (class "Default")
      (node (ref "Z1") (pin "110") (pinfunction "110_110") (pintype "passive+no_connect"))
    )
    (net (code "312") (name "unconnected-(Z1-Pad111)") (class "Default")
      (node (ref "Z1") (pin "111") (pinfunction "111_111") (pintype "passive+no_connect"))
    )
    (net (code "313") (name "unconnected-(Z1-Pad112)") (class "Default")
      (node (ref "Z1") (pin "112") (pinfunction "112_112") (pintype "passive+no_connect"))
    )
    (net (code "314") (name "unconnected-(Z1-Pad114)") (class "Default")
      (node (ref "Z1") (pin "114") (pinfunction "114_114") (pintype "passive+no_connect"))
    )
    (net (code "315") (name "unconnected-(Z1-Pad116)") (class "Default")
      (node (ref "Z1") (pin "116") (pinfunction "116_116") (pintype "passive+no_connect"))
    )
  )
)
